# powersupply.net
KiCad netlist of a schematic drawn in EAGLE
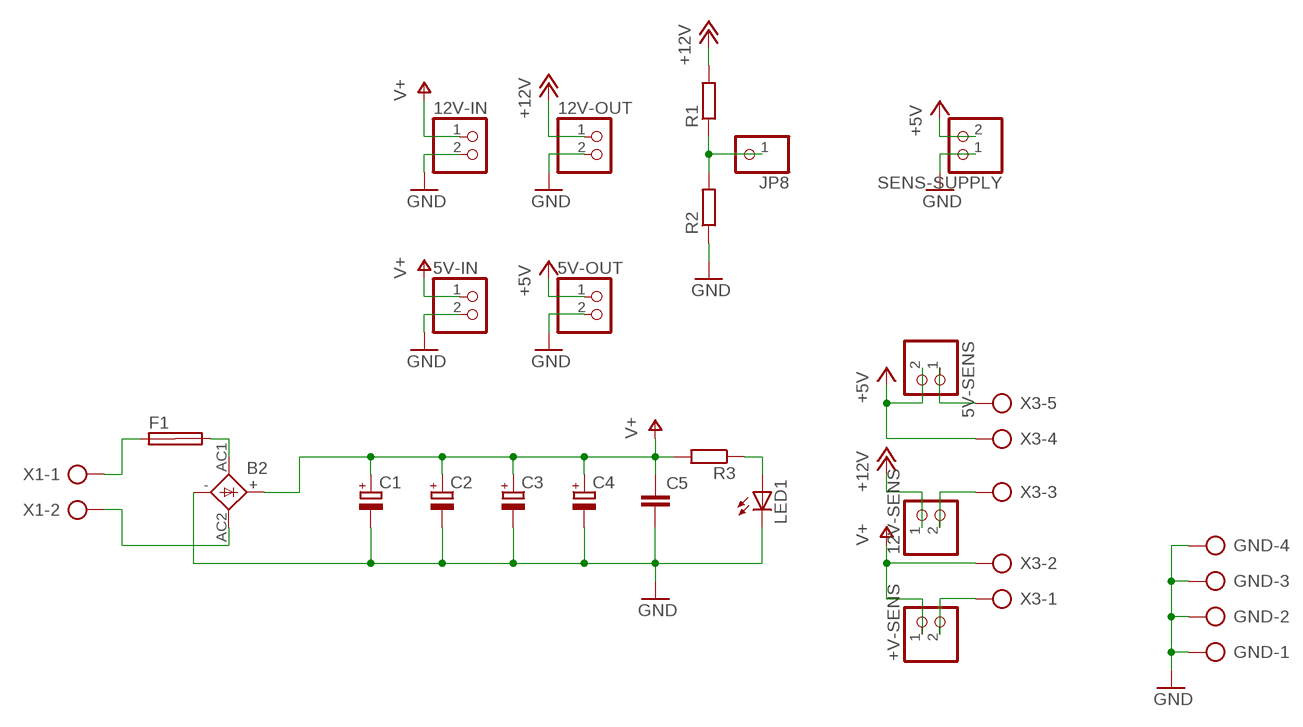
[diagram p0: schematic, sheet 1]

(export (version "E")
  (design (tool "Eeschema 10.0.6"))
  (components
    (comp (ref "+V-SENS")
      (value "PINHD-1X2")
      (footprint "eagle-import:1X02")
      (libsource (lib "eagle-import") (part "PINHD-1X2"))
    )
    (comp (ref "5V-IN")
      (value "PINHD-1X2")
      (footprint "eagle-import:1X02")
      (libsource (lib "eagle-import") (part "PINHD-1X2"))
    )
    (comp (ref "5V-OUT")
      (value "PINHD-1X2")
      (footprint "eagle-import:1X02")
      (libsource (lib "eagle-import") (part "PINHD-1X2"))
    )
    (comp (ref "5V-SENS")
      (value "PINHD-1X2")
      (footprint "eagle-import:1X02")
      (libsource (lib "eagle-import") (part "PINHD-1X2"))
    )
    (comp (ref "12V-IN")
      (value "PINHD-1X2")
      (footprint "eagle-import:1X02")
      (libsource (lib "eagle-import") (part "PINHD-1X2"))
    )
    (comp (ref "12V-OUT")
      (value "PINHD-1X2")
      (footprint "eagle-import:1X02")
      (libsource (lib "eagle-import") (part "PINHD-1X2"))
    )
    (comp (ref "12V-SENS")
      (value "PINHD-1X2")
      (footprint "eagle-import:1X02")
      (libsource (lib "eagle-import") (part "PINHD-1X2"))
    )
    (comp (ref "B2")
      (value "FB32")
      (footprint "eagle-import:FB32")
      (libsource (lib "eagle-import") (part "FB32"))
    )
    (comp (ref "C1")
      (value "CPOL-EUE5-13")
      (footprint "eagle-import:E5-13")
      (libsource (lib "eagle-import") (part "CPOL-EUE5-13"))
    )
    (comp (ref "C2")
      (value "CPOL-EUE5-13")
      (footprint "eagle-import:E5-13")
      (libsource (lib "eagle-import") (part "CPOL-EUE5-13"))
    )
    (comp (ref "C3")
      (value "CPOL-EUE5-13")
      (footprint "eagle-import:E5-13")
      (libsource (lib "eagle-import") (part "CPOL-EUE5-13"))
    )
    (comp (ref "C4")
      (value "CPOL-EUE5-13")
      (footprint "eagle-import:E5-13")
      (libsource (lib "eagle-import") (part "CPOL-EUE5-13"))
    )
    (comp (ref "C5")
      (value "C-EU025-025X050")
      (footprint "eagle-import:C025-025X050")
      (libsource (lib "eagle-import") (part "C-EU025-025X050"))
    )
    (comp (ref "F1")
      (value "SHK20L")
      (footprint "eagle-import:SHK20L")
      (libsource (lib "eagle-import") (part "SHK20L"))
    )
    (comp (ref "GND")
      (value "AK300/4")
      (footprint "eagle-import:AK300_4")
      (libsource (lib "eagle-import") (part "AK300/4"))
    )
    (comp (ref "JP8")
      (value "PINHD-1X1")
      (footprint "eagle-import:1X01")
      (libsource (lib "eagle-import") (part "PINHD-1X1"))
    )
    (comp (ref "LED1")
      (value "LEDB152")
      (footprint "eagle-import:Q62902-B152")
      (libsource (lib "eagle-import") (part "LEDB152"))
    )
    (comp (ref "R1")
      (value "R-EU_R1206")
      (footprint "eagle-import:R1206")
      (libsource (lib "eagle-import") (part "R-EU_R1206"))
    )
    (comp (ref "R2")
      (value "R-EU_R1206")
      (footprint "eagle-import:R1206")
      (libsource (lib "eagle-import") (part "R-EU_R1206"))
    )
    (comp (ref "R3")
      (value "R-EU_R1206")
      (footprint "eagle-import:R1206")
      (libsource (lib "eagle-import") (part "R-EU_R1206"))
    )
    (comp (ref "SENS-SUPPLY")
      (value "PINHD-1X2")
      (footprint "eagle-import:1X02")
      (libsource (lib "eagle-import") (part "PINHD-1X2"))
    )
    (comp (ref "X1")
      (value "AK300/2")
      (footprint "eagle-import:AK300_2")
      (libsource (lib "eagle-import") (part "AK300/2"))
    )
    (comp (ref "X3")
      (value "AK300/5")
      (footprint "eagle-import:AK300_5")
      (libsource (lib "eagle-import") (part "AK300/5"))
    )
  )
  (nets
    (net (code "1") (name "+5V") (class "Default")
      (node (ref "5V-OUT") (pin "1") (pinfunction "1_1") (pintype "passive"))
      (node (ref "5V-SENS") (pin "2") (pinfunction "2_2") (pintype "passive"))
      (node (ref "SENS-SUPPLY") (pin "2") (pinfunction "2_2") (pintype "passive"))
      (node (ref "X3") (pin "4") (pinfunction "KL_4") (pintype "passive"))
    )
    (net (code "2") (name "+12V") (class "Default")
      (node (ref "12V-OUT") (pin "1") (pinfunction "1_1") (pintype "passive"))
      (node (ref "12V-SENS") (pin "1") (pinfunction "1_1") (pintype "passive"))
      (node (ref "R1") (pin "2") (pinfunction "2_2") (pintype "passive"))
    )
    (net (code "3") (name "GND") (class "Default")
      (node (ref "12V-IN") (pin "2") (pinfunction "2_2") (pintype "passive"))
      (node (ref "12V-OUT") (pin "2") (pinfunction "2_2") (pintype "passive"))
      (node (ref "5V-IN") (pin "2") (pinfunction "2_2") (pintype "passive"))
      (node (ref "5V-OUT") (pin "2") (pinfunction "2_2") (pintype "passive"))
      (node (ref "B2") (pin "-") (pinfunction "-_-") (pintype "passive"))
      (node (ref "C1") (pin "-") (pinfunction "-_-") (pintype "passive"))
      (node (ref "C2") (pin "-") (pinfunction "-_-") (pintype "passive"))
      (node (ref "C3") (pin "-") (pinfunction "-_-") (pintype "passive"))
      (node (ref "C4") (pin "-") (pinfunction "-_-") (pintype "passive"))
      (node (ref "C5") (pin "2") (pinfunction "2_2") (pintype "passive"))
      (node (ref "GND") (pin "1") (pinfunction "KL_1") (pintype "passive"))
      (node (ref "GND") (pin "2") (pinfunction "KL_2") (pintype "passive"))
      (node (ref "GND") (pin "3") (pinfunction "KL_3") (pintype "passive"))
      (node (ref "GND") (pin "4") (pinfunction "KL_4") (pintype "passive"))
      (node (ref "LED1") (pin "K") (pinfunction "C_K") (pintype "passive"))
      (node (ref "R2") (pin "1") (pinfunction "1_1") (pintype "passive"))
      (node (ref "SENS-SUPPLY") (pin "1") (pinfunction "1_1") (pintype "passive"))
    )
    (net (code "4") (name "Net-(B2-PadAC1)") (class "Default")
      (node (ref "B2") (pin "AC1") (pinfunction "AC1_AC1") (pintype "passive"))
      (node (ref "F1") (pin "2A") (pinfunction "2A_2A") (pintype "passive"))
    )
    (net (code "5") (name "Net-(JP8-Pad1)") (class "Default")
      (node (ref "JP8") (pin "1") (pinfunction "1_1") (pintype "passive"))
      (node (ref "R1") (pin "1") (pinfunction "1_1") (pintype "passive"))
      (node (ref "R2") (pin "2") (pinfunction "2_2") (pintype "passive"))
    )
    (net (code "6") (name "Net-(LED1-PadA)") (class "Default")
      (node (ref "LED1") (pin "A") (pinfunction "A_A") (pintype "passive"))
      (node (ref "R3") (pin "1") (pinfunction "1_1") (pintype "passive"))
    )
    (net (code "7") (name "Net-(X1A-KL)") (class "Default")
      (node (ref "F1") (pin "1A") (pinfunction "1A_1A") (pintype "passive"))
      (node (ref "X1") (pin "1") (pinfunction "KL_1") (pintype "passive"))
    )
    (net (code "8") (name "Net-(X1B-KL)") (class "Default")
      (node (ref "B2") (pin "AC2") (pinfunction "AC2_AC2") (pintype "passive"))
      (node (ref "X1") (pin "2") (pinfunction "KL_2") (pintype "passive"))
    )
    (net (code "9") (name "Net-(X3A-KL)") (class "Default")
      (node (ref "+V-SENS") (pin "2") (pinfunction "2_2") (pintype "passive"))
      (node (ref "X3") (pin "1") (pinfunction "KL_1") (pintype "passive"))
    )
    (net (code "10") (name "Net-(X3C-KL)") (class "Default")
      (node (ref "12V-SENS") (pin "2") (pinfunction "2_2") (pintype "passive"))
      (node (ref "X3") (pin "3") (pinfunction "KL_3") (pintype "passive"))
    )
    (net (code "11") (name "Net-(X3E-KL)") (class "Default")
      (node (ref "5V-SENS") (pin "1") (pinfunction "1_1") (pintype "passive"))
      (node (ref "X3") (pin "5") (pinfunction "KL_5") (pintype "passive"))
    )
    (net (code "12") (name "V+") (class "Default")
      (node (ref "+V-SENS") (pin "1") (pinfunction "1_1") (pintype "passive"))
      (node (ref "12V-IN") (pin "1") (pinfunction "1_1") (pintype "passive"))
      (node (ref "5V-IN") (pin "1") (pinfunction "1_1") (pintype "passive"))
      (node (ref "B2") (pin "+") (pinfunction "+_+") (pintype "passive"))
      (node (ref "C1") (pin "+") (pinfunction "+_+") (pintype "passive"))
      (node (ref "C2") (pin "+") (pinfunction "+_+") (pintype "passive"))
      (node (ref "C3") (pin "+") (pinfunction "+_+") (pintype "passive"))
      (node (ref "C4") (pin "+") (pinfunction "+_+") (pintype "passive"))
      (node (ref "C5") (pin "1") (pinfunction "1_1") (pintype "passive"))
      (node (ref "R3") (pin "2") (pinfunction "2_2") (pintype "passive"))
      (node (ref "X3") (pin "2") (pinfunction "KL_2") (pintype "passive"))
    )
    (net (code "13") (name "unconnected-(F1-Pad1B)") (class "Default")
      (node (ref "F1") (pin "1B") (pinfunction "1B_1B") (pintype "passive"))
    )
    (net (code "14") (name "unconnected-(F1-Pad2B)") (class "Default")
      (node (ref "F1") (pin "2B") (pinfunction "2B_2B") (pintype "passive"))
    )
  )
)
